# 6coils-1-discrete.net
KiCad netlist of a schematic drawn in EasyEDA
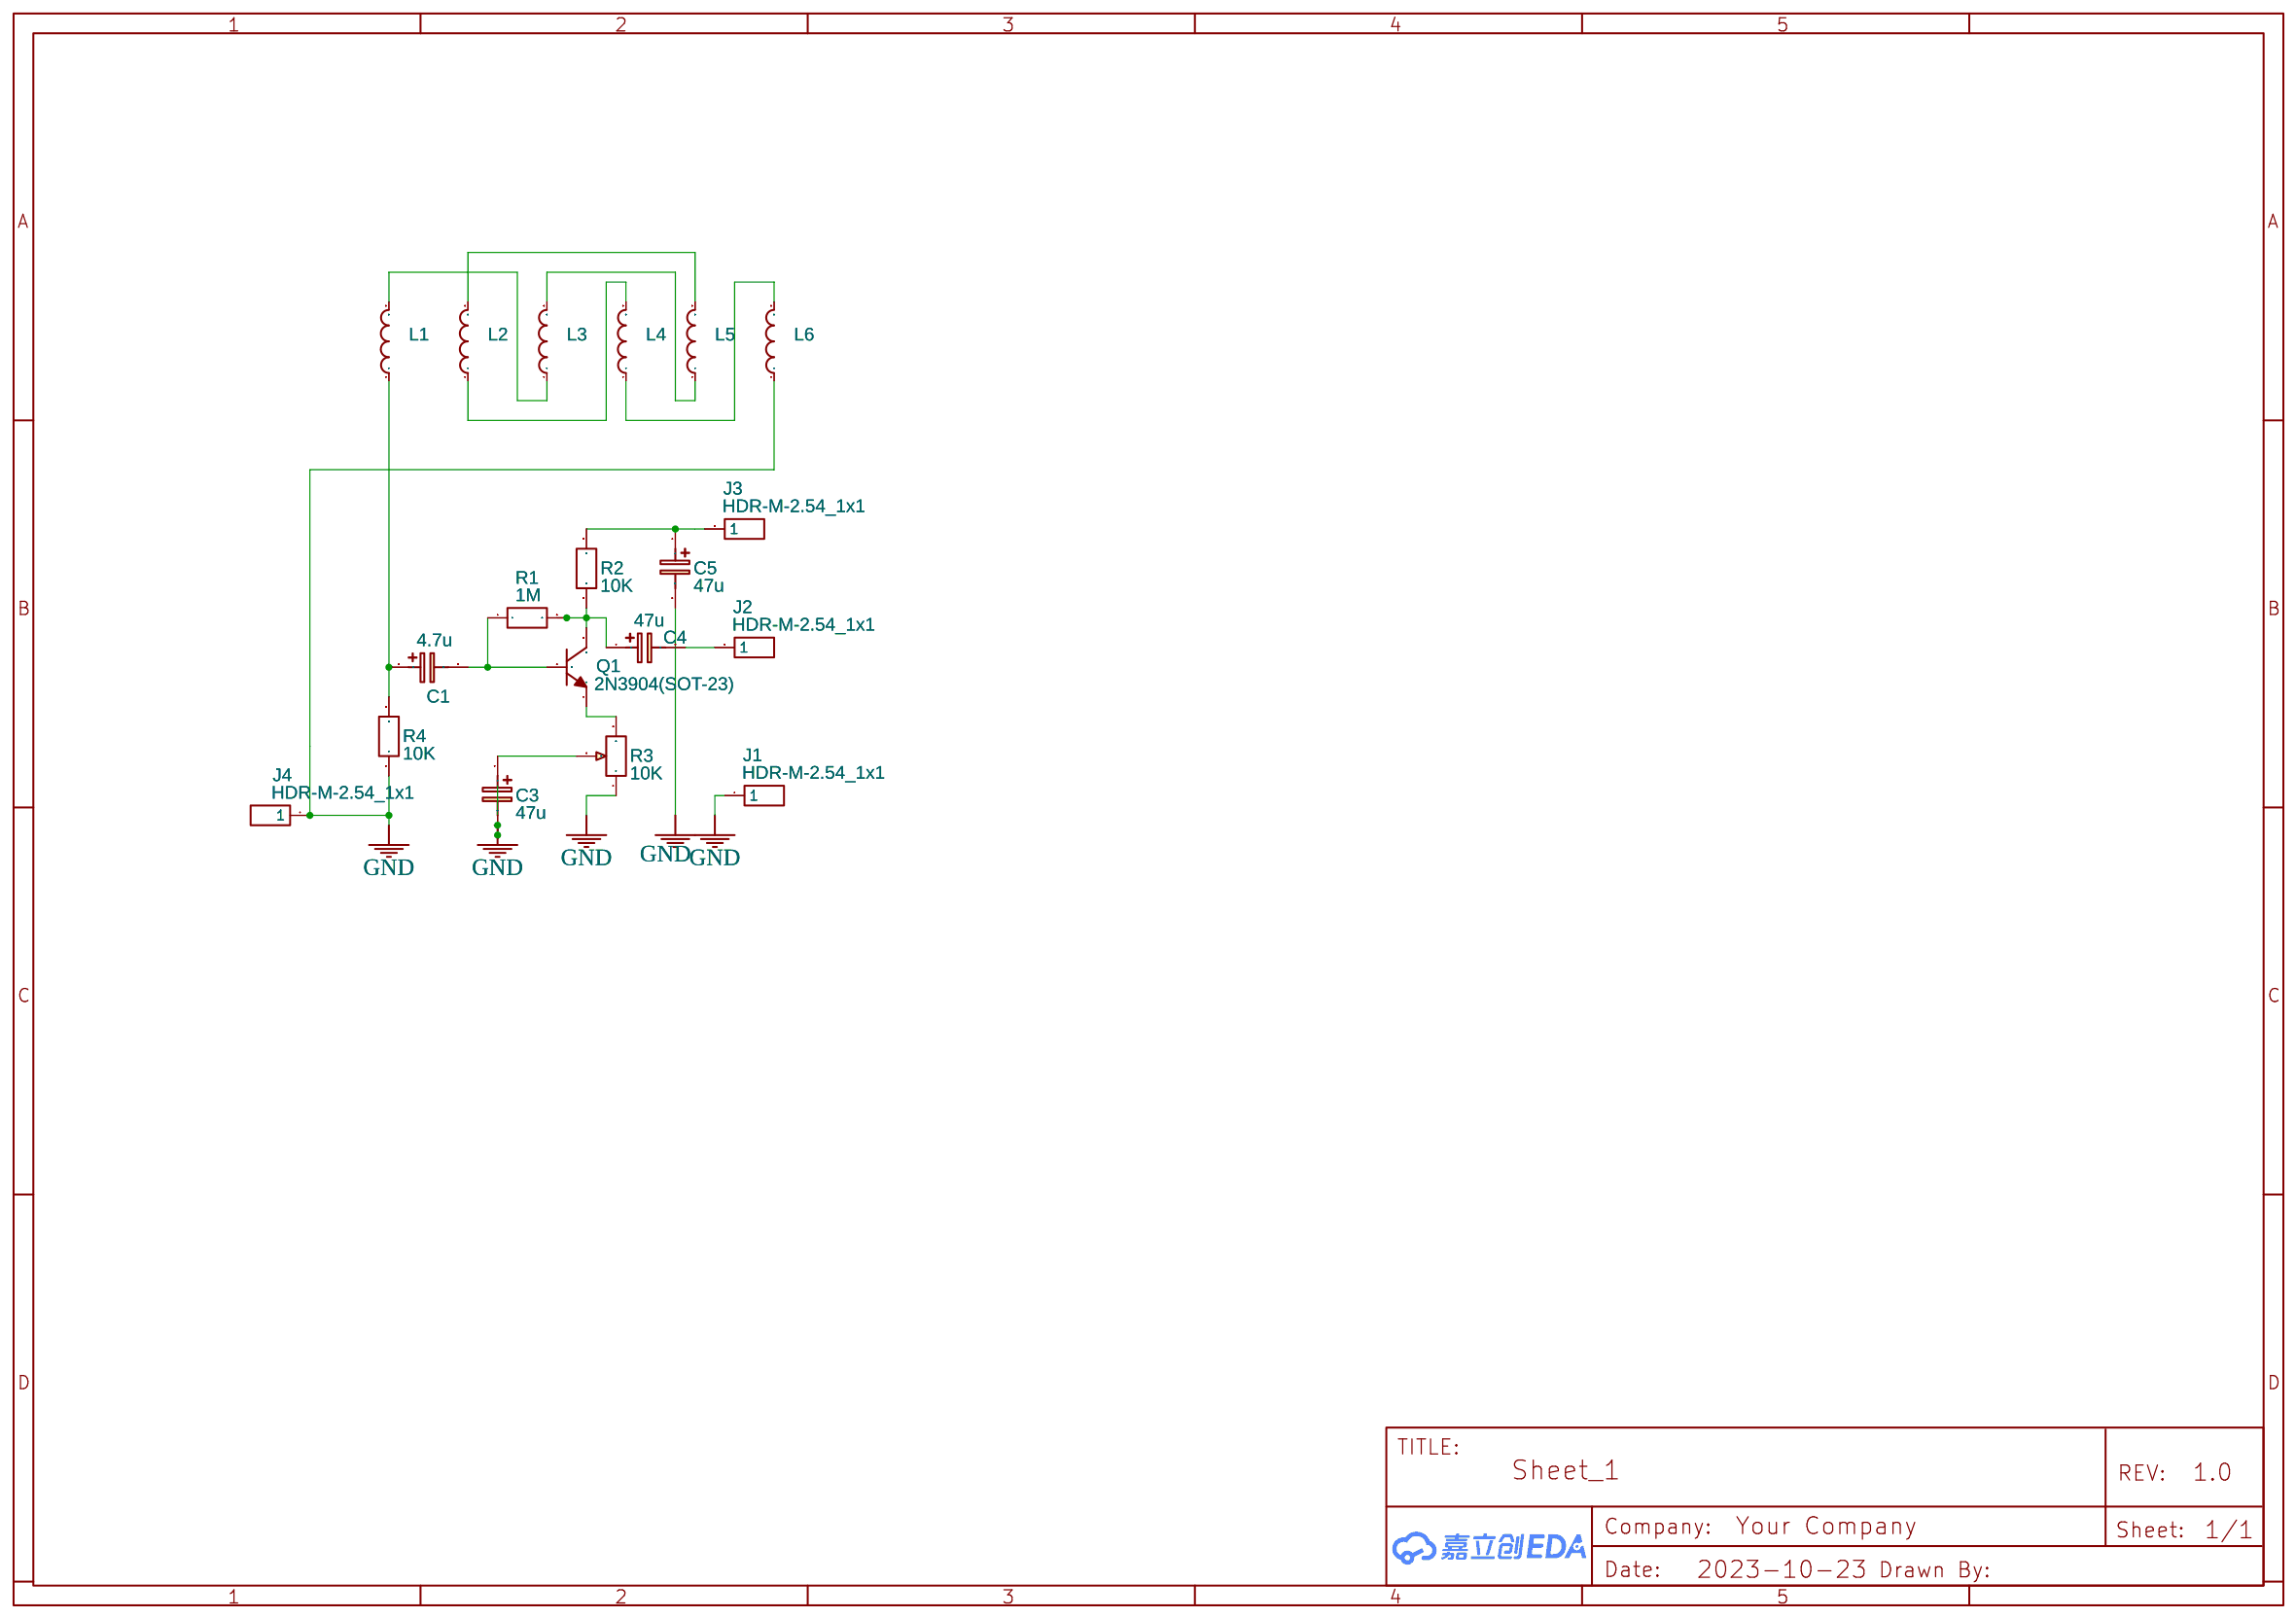
[diagram p0: schematic sheet]

(export (version "E")
  (design (tool "Eeschema 10.0.6"))
  (components
    (comp (ref "C1") (value "4.7u") (libsource (lib "") (part "C_Tan_SMD_A_EU")))
    (comp (ref "C3") (value "47u") (libsource (lib "") (part "C_Tan_SMD_A_EU_2")))
    (comp (ref "C4") (value "47u") (libsource (lib "") (part "C_Tan_SMD_A_EU_1")))
    (comp (ref "C5") (value "47u") (libsource (lib "") (part "C_Tan_SMD_A_EU_3")))
    (comp (ref "J1")
      (value "HDR-M-2.54_1x1")
      (fields (field (name "BOM_Supplier Part") "C81276"))
      (libsource (lib "") (part "HDR-M-2.54_1x1"))
    )
    (comp (ref "J2")
      (value "HDR-M-2.54_1x1")
      (fields (field (name "BOM_Supplier Part") "C81276"))
      (libsource (lib "") (part "HDR-M-2.54_1x1"))
    )
    (comp (ref "J3")
      (value "HDR-M-2.54_1x1")
      (fields (field (name "BOM_Supplier Part") "C81276"))
      (libsource (lib "") (part "HDR-M-2.54_1x1"))
    )
    (comp (ref "J4")
      (value "HDR-M-2.54_1x1")
      (fields (field (name "BOM_Supplier Part") "C81276"))
      (libsource (lib "") (part "HDR-M-2.54_1x1_1"))
    )
    (comp (ref "L1")
      (value "INDUCTOR_SMD:L_COILCRAFT_XXL4040")
      (fields (field (name "Manufacturer Part") "Inductor_SMD:L_Coilcraft_XxL4040"))
      (libsource (lib "") (part "INDUCTOR_SMD{colon}L_COILCRAFT_XXL4040_1"))
    )
    (comp (ref "L2")
      (value "INDUCTOR_SMD:L_COILCRAFT_XXL4040")
      (fields (field (name "Manufacturer Part") "Inductor_SMD:L_Coilcraft_XxL4040"))
      (libsource (lib "") (part "INDUCTOR_SMD{colon}L_COILCRAFT_XXL4040_1"))
    )
    (comp (ref "L3")
      (value "INDUCTOR_SMD:L_COILCRAFT_XXL4040")
      (fields (field (name "Manufacturer Part") "Inductor_SMD:L_Coilcraft_XxL4040"))
      (libsource (lib "") (part "INDUCTOR_SMD{colon}L_COILCRAFT_XXL4040"))
    )
    (comp (ref "L4")
      (value "INDUCTOR_SMD:L_COILCRAFT_XXL4040")
      (fields (field (name "Manufacturer Part") "Inductor_SMD:L_Coilcraft_XxL4040"))
      (libsource (lib "") (part "INDUCTOR_SMD{colon}L_COILCRAFT_XXL4040"))
    )
    (comp (ref "L5")
      (value "INDUCTOR_SMD:L_COILCRAFT_XXL4040")
      (fields (field (name "Manufacturer Part") "Inductor_SMD:L_Coilcraft_XxL4040"))
      (libsource (lib "") (part "INDUCTOR_SMD{colon}L_COILCRAFT_XXL4040"))
    )
    (comp (ref "L6")
      (value "INDUCTOR_SMD:L_COILCRAFT_XXL4040")
      (fields (field (name "Manufacturer Part") "Inductor_SMD:L_Coilcraft_XxL4040"))
      (libsource (lib "") (part "INDUCTOR_SMD{colon}L_COILCRAFT_XXL4040"))
    )
    (comp (ref "Q1")
      (value "2N3904(SOT-23)")
      (fields
        (field (name "BOM_Manufacturer Part") "2n3904S-RTK/PS")
        (field (name "BOM_Supplier Part") "C18536")
      )
      (libsource (lib "") (part "2N3904(SOT-23)"))
    )
    (comp (ref "R1") (value "1M") (libsource (lib "") (part "R_0603_EU_1")))
    (comp (ref "R2") (value "10K") (libsource (lib "") (part "R_0603_EU")))
    (comp (ref "R3")
      (value "10K")
      (fields (field (name "Manufacturer Part") "RM063-103 10K") (field (name "Manufacturer") "JML"))
      (libsource (lib "") (part "RM063-103 10K"))
    )
    (comp (ref "R4") (value "10K") (libsource (lib "") (part "R_0603_EU")))
  )
  (nets
    (net (code "1") (name "GND") (class "Default")
      (node (ref "C3") (pin "2") (pinfunction "2_2") (pintype "unspecified"))
      (node (ref "C5") (pin "2") (pinfunction "2_2") (pintype "unspecified"))
      (node (ref "J1") (pin "1") (pinfunction "1_1") (pintype "input"))
      (node (ref "J4") (pin "1") (pinfunction "1_1") (pintype "input"))
      (node (ref "L6") (pin "1") (pinfunction "1_1") (pintype "unspecified"))
      (node (ref "R3") (pin "1") (pinfunction "1_1") (pintype "input"))
      (node (ref "R4") (pin "1") (pinfunction "1_1") (pintype "unspecified"))
    )
    (net (code "2") (name "Net-(C1-Pad1)") (class "Default")
      (node (ref "C1") (pin "1") (pinfunction "1_1") (pintype "unspecified"))
      (node (ref "L1") (pin "1") (pinfunction "1_1") (pintype "unspecified"))
      (node (ref "R4") (pin "2") (pinfunction "2_2") (pintype "unspecified"))
    )
    (net (code "3") (name "Net-(C3-Pad1)") (class "Default")
      (node (ref "C3") (pin "1") (pinfunction "1_1") (pintype "unspecified"))
      (node (ref "R3") (pin "2") (pinfunction "2_2") (pintype "input"))
    )
    (net (code "4") (name "Net-(C4-Pad2)") (class "Default")
      (node (ref "C4") (pin "2") (pinfunction "2_2") (pintype "unspecified"))
      (node (ref "J2") (pin "1") (pinfunction "1_1") (pintype "input"))
    )
    (net (code "5") (name "Net-(C5-Pad1)") (class "Default")
      (node (ref "C5") (pin "1") (pinfunction "1_1") (pintype "unspecified"))
      (node (ref "J3") (pin "1") (pinfunction "1_1") (pintype "input"))
      (node (ref "R2") (pin "2") (pinfunction "2_2") (pintype "unspecified"))
    )
    (net (code "6") (name "Net-(L1-Pad2)") (class "Default")
      (node (ref "L1") (pin "2") (pinfunction "2_2") (pintype "unspecified"))
      (node (ref "L3") (pin "1") (pinfunction "1_1") (pintype "unspecified"))
    )
    (net (code "7") (name "Net-(L2-Pad1)") (class "Default")
      (node (ref "L2") (pin "1") (pinfunction "1_1") (pintype "unspecified"))
      (node (ref "L4") (pin "2") (pinfunction "2_2") (pintype "unspecified"))
    )
    (net (code "8") (name "Net-(L2-Pad2)") (class "Default")
      (node (ref "L2") (pin "2") (pinfunction "2_2") (pintype "unspecified"))
      (node (ref "L5") (pin "2") (pinfunction "2_2") (pintype "unspecified"))
    )
    (net (code "9") (name "Net-(L3-Pad2)") (class "Default")
      (node (ref "L3") (pin "2") (pinfunction "2_2") (pintype "unspecified"))
      (node (ref "L5") (pin "1") (pinfunction "1_1") (pintype "unspecified"))
    )
    (net (code "10") (name "Net-(L4-Pad1)") (class "Default")
      (node (ref "L4") (pin "1") (pinfunction "1_1") (pintype "unspecified"))
      (node (ref "L6") (pin "2") (pinfunction "2_2") (pintype "unspecified"))
    )
    (net (code "11") (name "Net-(Q1-B)") (class "Default")
      (node (ref "C1") (pin "2") (pinfunction "2_2") (pintype "unspecified"))
      (node (ref "Q1") (pin "2") (pinfunction "B_2") (pintype "input"))
      (node (ref "R1") (pin "1") (pinfunction "1_1") (pintype "unspecified"))
    )
    (net (code "12") (name "Net-(Q1-C)") (class "Default")
      (node (ref "C4") (pin "1") (pinfunction "1_1") (pintype "unspecified"))
      (node (ref "Q1") (pin "3") (pinfunction "C_3") (pintype "input"))
      (node (ref "R1") (pin "2") (pinfunction "2_2") (pintype "unspecified"))
      (node (ref "R2") (pin "1") (pinfunction "1_1") (pintype "unspecified"))
    )
    (net (code "13") (name "Net-(Q1-E)") (class "Default")
      (node (ref "Q1") (pin "1") (pinfunction "E_1") (pintype "input"))
      (node (ref "R3") (pin "3") (pinfunction "3_3") (pintype "input"))
    )
  )
)
